# Sheet4.net
KiCad netlist of a schematic drawn in Altium Designer
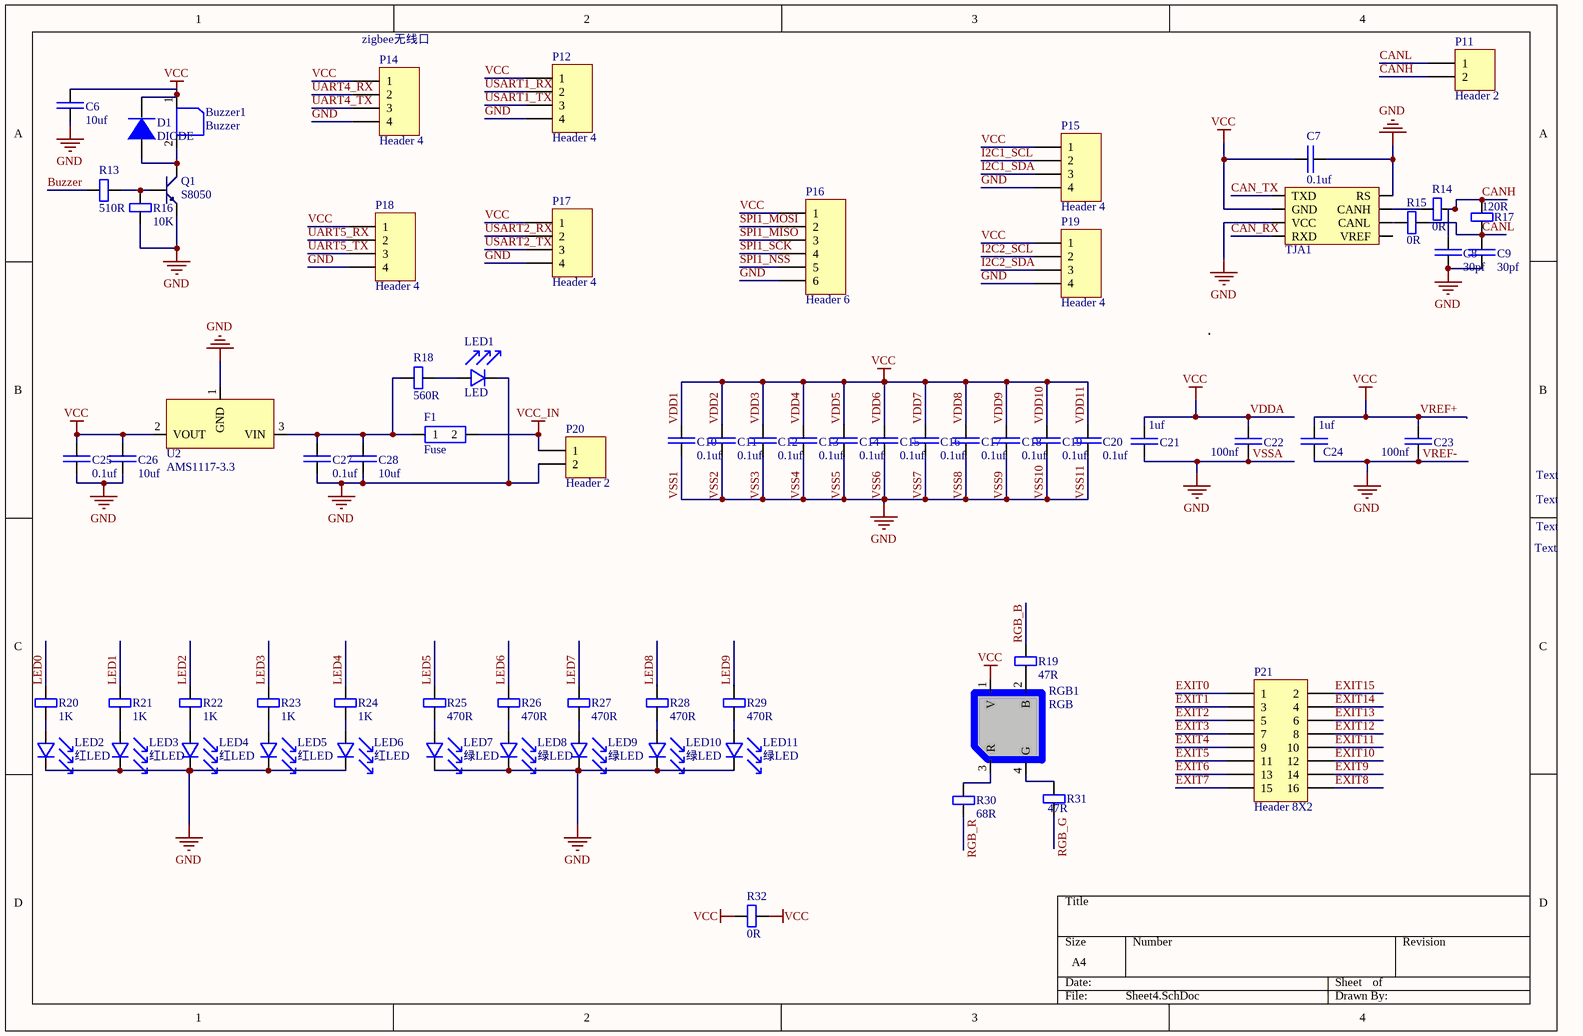
[diagram p0: Sheet4.SchDoc]

(export (version "E")
  (design (tool "Eeschema 10.0.6"))
  (components
    (comp (ref "Buzzer1") (value "Buzzer") (footprint "BUZZER") (libsource (lib "Schlib1") (part "Buzzer")))
    (comp (ref "C6") (value "10uf") (footprint "0402") (libsource (lib "Schlib1") (part "C")))
    (comp (ref "C7") (value "0.1uf") (footprint "0402") (libsource (lib "Schlib1") (part "C")))
    (comp (ref "C8") (value "30pf") (footprint "0402") (libsource (lib "Schlib1") (part "C")))
    (comp (ref "C9") (value "30pf") (footprint "0402") (libsource (lib "Schlib1") (part "C")))
    (comp (ref "C10") (value "0.1uf") (footprint "0402") (libsource (lib "Schlib1") (part "C")))
    (comp (ref "C11") (value "0.1uf") (footprint "0402") (libsource (lib "Schlib1") (part "C")))
    (comp (ref "C12") (value "0.1uf") (footprint "0402") (libsource (lib "Schlib1") (part "C")))
    (comp (ref "C13") (value "0.1uf") (footprint "0402") (libsource (lib "Schlib1") (part "C")))
    (comp (ref "C14") (value "0.1uf") (footprint "0402") (libsource (lib "Schlib1") (part "C")))
    (comp (ref "C15") (value "0.1uf") (footprint "0402") (libsource (lib "Schlib1") (part "C")))
    (comp (ref "C16") (value "0.1uf") (footprint "0402") (libsource (lib "Schlib1") (part "C")))
    (comp (ref "C17") (value "0.1uf") (footprint "0402") (libsource (lib "Schlib1") (part "C")))
    (comp (ref "C18") (value "0.1uf") (footprint "0402") (libsource (lib "Schlib1") (part "C")))
    (comp (ref "C19") (value "0.1uf") (footprint "0402") (libsource (lib "Schlib1") (part "C")))
    (comp (ref "C20") (value "0.1uf") (footprint "0402") (libsource (lib "Schlib1") (part "C")))
    (comp (ref "C21") (value "1uf") (footprint "0402") (libsource (lib "Schlib1") (part "C")))
    (comp (ref "C22") (value "100nf") (footprint "0402") (libsource (lib "Schlib1") (part "C")))
    (comp (ref "C23") (value "100nf") (footprint "0402") (libsource (lib "Schlib1") (part "C")))
    (comp (ref "C24") (value "1uf") (footprint "0402") (libsource (lib "Schlib1") (part "C")))
    (comp (ref "C25") (value "0.1uf") (footprint "0402") (libsource (lib "Schlib1") (part "C")))
    (comp (ref "C26") (value "10uf") (footprint "0402") (libsource (lib "Schlib1") (part "C")))
    (comp (ref "C27") (value "0.1uf") (footprint "0402") (libsource (lib "Schlib1") (part "C")))
    (comp (ref "C28") (value "10uf") (footprint "0402") (libsource (lib "Schlib1") (part "C")))
    (comp (ref "D1") (value "DIODE") (footprint "DIODE") (libsource (lib "Schlib1") (part "DIODE")))
    (comp (ref "F1") (value "Fuse") (footprint "0805") (libsource (lib "Schlib1") (part "Fuse")))
    (comp (ref "LED1") (value "LED") (footprint "0603") (libsource (lib "Schlib1") (part "LED")))
    (comp (ref "LED2") (value "红LED") (footprint "0603") (libsource (lib "Schlib1") (part "LED")))
    (comp (ref "LED3") (value "红LED") (footprint "0603") (libsource (lib "Schlib1") (part "LED")))
    (comp (ref "LED4") (value "红LED") (footprint "0603") (libsource (lib "Schlib1") (part "LED")))
    (comp (ref "LED5") (value "红LED") (footprint "0603") (libsource (lib "Schlib1") (part "LED")))
    (comp (ref "LED6") (value "红LED") (footprint "0603") (libsource (lib "Schlib1") (part "LED")))
    (comp (ref "LED7") (value "绿LED") (footprint "0603") (libsource (lib "Schlib1") (part "LED")))
    (comp (ref "LED8") (value "绿LED") (footprint "0603") (libsource (lib "Schlib1") (part "LED")))
    (comp (ref "LED9") (value "绿LED") (footprint "0603") (libsource (lib "Schlib1") (part "LED")))
    (comp (ref "LED10") (value "绿LED") (footprint "0603") (libsource (lib "Schlib1") (part "LED")))
    (comp (ref "LED11") (value "绿LED") (footprint "0603") (libsource (lib "Schlib1") (part "LED")))
    (comp (ref "P11")
      (value "Header 2")
      (footprint "GH1.25_2P")
      (description "Header, 2-Pin")
      (fields (field (name "PUBLISHER") "Altium Limited"))
      (libsource (lib "Miscellaneous Connectors") (part "Header 2"))
    )
    (comp (ref "P12")
      (value "Header 4")
      (footprint "GH1.25_4P")
      (description "Header, 4-Pin")
      (fields (field (name "PUBLISHER") "Altium Limited"))
      (libsource (lib "Miscellaneous Connectors") (part "Header 4"))
    )
    (comp (ref "P14")
      (value "Header 4")
      (footprint "GH1.25_4P")
      (description "Header, 4-Pin")
      (fields (field (name "PUBLISHER") "Altium Limited"))
      (libsource (lib "Miscellaneous Connectors") (part "Header 4"))
    )
    (comp (ref "P15")
      (value "Header 4")
      (footprint "GH1.25_4P")
      (description "Header, 4-Pin")
      (fields (field (name "PUBLISHER") "Altium Limited"))
      (libsource (lib "Miscellaneous Connectors") (part "Header 4"))
    )
    (comp (ref "P16")
      (value "Header 6")
      (footprint "HDR1X6")
      (description "Header, 6-Pin")
      (fields (field (name "PUBLISHER") "Altium Limited"))
      (libsource (lib "Miscellaneous Connectors") (part "Header 6"))
    )
    (comp (ref "P17")
      (value "Header 4")
      (footprint "GH1.25_4P")
      (description "Header, 4-Pin")
      (fields (field (name "PUBLISHER") "Altium Limited"))
      (libsource (lib "Miscellaneous Connectors") (part "Header 4"))
    )
    (comp (ref "P18")
      (value "Header 4")
      (footprint "GH1.25_4P")
      (description "Header, 4-Pin")
      (fields (field (name "PUBLISHER") "Altium Limited"))
      (libsource (lib "Miscellaneous Connectors") (part "Header 4"))
    )
    (comp (ref "P19")
      (value "Header 4")
      (footprint "GH1.25_4P")
      (description "Header, 4-Pin")
      (fields (field (name "PUBLISHER") "Altium Limited"))
      (libsource (lib "Miscellaneous Connectors") (part "Header 4"))
    )
    (comp (ref "P20")
      (value "Header 2")
      (footprint "XT30-PW-M")
      (description "Header, 2-Pin")
      (fields (field (name "PUBLISHER") "Altium Limited"))
      (libsource (lib "Miscellaneous Connectors") (part "Header 2"))
    )
    (comp (ref "P21")
      (value "Header 8X2")
      (footprint "HDR2X8")
      (description "Header, 8-Pin, Dual row")
      (fields (field (name "PUBLISHER") "Altium Limited"))
      (libsource (lib "Miscellaneous Connectors") (part "Header 8X2"))
    )
    (comp (ref "Q1")
      (value "S8050")
      (footprint "SOT-23R")
      (description "8050/BCW846/BCW847")
      (libsource (lib "REMOTOR V1.6") (part "NPN"))
    )
    (comp (ref "R13") (value "510R") (footprint "0402") (libsource (lib "Schlib1") (part "R")))
    (comp (ref "R14") (value "0R") (footprint "0402") (libsource (lib "Schlib1") (part "R")))
    (comp (ref "R15") (value "0R") (footprint "0402") (libsource (lib "Schlib1") (part "R")))
    (comp (ref "R16") (value "10K") (footprint "0402") (libsource (lib "Schlib1") (part "R")))
    (comp (ref "R17") (value "120R") (footprint "0402") (libsource (lib "Schlib1") (part "R")))
    (comp (ref "R18") (value "560R") (footprint "0402") (libsource (lib "Schlib1") (part "R")))
    (comp (ref "R19") (value "47R") (footprint "0402") (libsource (lib "Schlib1") (part "R")))
    (comp (ref "R20") (value "1K") (footprint "0402") (libsource (lib "Schlib1") (part "R")))
    (comp (ref "R21") (value "1K") (footprint "0402") (libsource (lib "Schlib1") (part "R")))
    (comp (ref "R22") (value "1K") (footprint "0402") (libsource (lib "Schlib1") (part "R")))
    (comp (ref "R23") (value "1K") (footprint "0402") (libsource (lib "Schlib1") (part "R")))
    (comp (ref "R24") (value "1K") (footprint "0402") (libsource (lib "Schlib1") (part "R")))
    (comp (ref "R25") (value "470R") (footprint "0402") (libsource (lib "Schlib1") (part "R")))
    (comp (ref "R26") (value "470R") (footprint "0402") (libsource (lib "Schlib1") (part "R")))
    (comp (ref "R27") (value "470R") (footprint "0402") (libsource (lib "Schlib1") (part "R")))
    (comp (ref "R28") (value "470R") (footprint "0402") (libsource (lib "Schlib1") (part "R")))
    (comp (ref "R29") (value "470R") (footprint "0402") (libsource (lib "Schlib1") (part "R")))
    (comp (ref "R30") (value "68R") (footprint "0402") (libsource (lib "Schlib1") (part "R")))
    (comp (ref "R31") (value "47R") (footprint "0402") (libsource (lib "Schlib1") (part "R")))
    (comp (ref "R32") (value "0R") (footprint "0603") (libsource (lib "Schlib1") (part "R")))
    (comp (ref "RGB1") (value "RGB") (footprint "RGB_LED") (libsource (lib "Schlib1") (part "RGB")))
    (comp (ref "TJA1") (value "TJA1050") (footprint "TJA1050") (libsource (lib "Schlib1") (part "TJA1050")))
    (comp (ref "U2")
      (value "AMS1117-3.3")
      (footprint "ASM1117")
      (libsource (lib "Schlib1") (part "AMS1117-3.3"))
    )
  )
  (nets
    (net (code "1") (name "/Buzzer") (class "Default")
      (node (ref "R13") (pin "1") (pinfunction "1_1") (pintype "passive"))
    )
    (net (code "2") (name "/CANH") (class "Default")
      (node (ref "C8") (pin "2") (pinfunction "2_2") (pintype "passive"))
      (node (ref "P11") (pin "2") (pinfunction "2_2") (pintype "passive"))
      (node (ref "R14") (pin "2") (pinfunction "2_2") (pintype "passive"))
      (node (ref "R17") (pin "2") (pinfunction "2_2") (pintype "passive"))
    )
    (net (code "3") (name "/CANL") (class "Default")
      (node (ref "C9") (pin "2") (pinfunction "2_2") (pintype "passive"))
      (node (ref "P11") (pin "1") (pinfunction "1_1") (pintype "passive"))
      (node (ref "R15") (pin "2") (pinfunction "2_2") (pintype "passive"))
      (node (ref "R17") (pin "1") (pinfunction "1_1") (pintype "passive"))
    )
    (net (code "4") (name "/CAN_RX") (class "Default")
      (node (ref "TJA1") (pin "4") (pinfunction "RXD_4") (pintype "passive"))
    )
    (net (code "5") (name "/CAN_TX") (class "Default")
      (node (ref "TJA1") (pin "1") (pinfunction "TXD_1") (pintype "passive"))
    )
    (net (code "6") (name "/EXIT0") (class "Default")
      (node (ref "P21") (pin "1") (pinfunction "1_1") (pintype "passive"))
    )
    (net (code "7") (name "/EXIT1") (class "Default")
      (node (ref "P21") (pin "3") (pinfunction "3_3") (pintype "passive"))
    )
    (net (code "8") (name "/EXIT2") (class "Default")
      (node (ref "P21") (pin "5") (pinfunction "5_5") (pintype "passive"))
    )
    (net (code "9") (name "/EXIT3") (class "Default")
      (node (ref "P21") (pin "7") (pinfunction "7_7") (pintype "passive"))
    )
    (net (code "10") (name "/EXIT4") (class "Default")
      (node (ref "P21") (pin "9") (pinfunction "9_9") (pintype "passive"))
    )
    (net (code "11") (name "/EXIT5") (class "Default")
      (node (ref "P21") (pin "11") (pinfunction "11_11") (pintype "passive"))
    )
    (net (code "12") (name "/EXIT6") (class "Default")
      (node (ref "P21") (pin "13") (pinfunction "13_13") (pintype "passive"))
    )
    (net (code "13") (name "/EXIT7") (class "Default")
      (node (ref "P21") (pin "15") (pinfunction "15_15") (pintype "passive"))
    )
    (net (code "14") (name "/EXIT8") (class "Default")
      (node (ref "P21") (pin "16") (pinfunction "16_16") (pintype "passive"))
    )
    (net (code "15") (name "/EXIT9") (class "Default")
      (node (ref "P21") (pin "14") (pinfunction "14_14") (pintype "passive"))
    )
    (net (code "16") (name "/EXIT10") (class "Default")
      (node (ref "P21") (pin "12") (pinfunction "12_12") (pintype "passive"))
    )
    (net (code "17") (name "/EXIT11") (class "Default")
      (node (ref "P21") (pin "10") (pinfunction "10_10") (pintype "passive"))
    )
    (net (code "18") (name "/EXIT12") (class "Default")
      (node (ref "P21") (pin "8") (pinfunction "8_8") (pintype "passive"))
    )
    (net (code "19") (name "/EXIT13") (class "Default")
      (node (ref "P21") (pin "6") (pinfunction "6_6") (pintype "passive"))
    )
    (net (code "20") (name "/EXIT14") (class "Default")
      (node (ref "P21") (pin "4") (pinfunction "4_4") (pintype "passive"))
    )
    (net (code "21") (name "/EXIT15") (class "Default")
      (node (ref "P21") (pin "2") (pinfunction "2_2") (pintype "passive"))
    )
    (net (code "22") (name "/I2C1_SCL") (class "Default")
      (node (ref "P15") (pin "2") (pinfunction "2_2") (pintype "passive"))
    )
    (net (code "23") (name "/I2C1_SDA") (class "Default")
      (node (ref "P15") (pin "3") (pinfunction "3_3") (pintype "passive"))
    )
    (net (code "24") (name "/I2C2_SCL") (class "Default")
      (node (ref "P19") (pin "2") (pinfunction "2_2") (pintype "passive"))
    )
    (net (code "25") (name "/I2C2_SDA") (class "Default")
      (node (ref "P19") (pin "3") (pinfunction "3_3") (pintype "passive"))
    )
    (net (code "26") (name "/LED0") (class "Default")
      (node (ref "R20") (pin "2") (pinfunction "2_2") (pintype "passive"))
    )
    (net (code "27") (name "/LED1") (class "Default")
      (node (ref "R21") (pin "2") (pinfunction "2_2") (pintype "passive"))
    )
    (net (code "28") (name "/LED2") (class "Default")
      (node (ref "R22") (pin "2") (pinfunction "2_2") (pintype "passive"))
    )
    (net (code "29") (name "/LED3") (class "Default")
      (node (ref "R23") (pin "2") (pinfunction "2_2") (pintype "passive"))
    )
    (net (code "30") (name "/LED4") (class "Default")
      (node (ref "R24") (pin "2") (pinfunction "2_2") (pintype "passive"))
    )
    (net (code "31") (name "/LED5") (class "Default")
      (node (ref "R25") (pin "2") (pinfunction "2_2") (pintype "passive"))
    )
    (net (code "32") (name "/LED6") (class "Default")
      (node (ref "R26") (pin "2") (pinfunction "2_2") (pintype "passive"))
    )
    (net (code "33") (name "/LED7") (class "Default")
      (node (ref "R27") (pin "2") (pinfunction "2_2") (pintype "passive"))
    )
    (net (code "34") (name "/LED8") (class "Default")
      (node (ref "R28") (pin "2") (pinfunction "2_2") (pintype "passive"))
    )
    (net (code "35") (name "/LED9") (class "Default")
      (node (ref "R29") (pin "2") (pinfunction "2_2") (pintype "passive"))
    )
    (net (code "36") (name "/RGB_B") (class "Default")
      (node (ref "R19") (pin "2") (pinfunction "2_2") (pintype "passive"))
    )
    (net (code "37") (name "/RGB_G") (class "Default")
      (node (ref "R31") (pin "1") (pinfunction "1_1") (pintype "passive"))
    )
    (net (code "38") (name "/RGB_R") (class "Default")
      (node (ref "R30") (pin "1") (pinfunction "1_1") (pintype "passive"))
    )
    (net (code "39") (name "/SPI1_MISO") (class "Default")
      (node (ref "P16") (pin "3") (pinfunction "3_3") (pintype "passive"))
    )
    (net (code "40") (name "/SPI1_MOSI") (class "Default")
      (node (ref "P16") (pin "2") (pinfunction "2_2") (pintype "passive"))
    )
    (net (code "41") (name "/SPI1_NSS") (class "Default")
      (node (ref "P16") (pin "5") (pinfunction "5_5") (pintype "passive"))
    )
    (net (code "42") (name "/SPI1_SCK") (class "Default")
      (node (ref "P16") (pin "4") (pinfunction "4_4") (pintype "passive"))
    )
    (net (code "43") (name "/UART4_RX") (class "Default")
      (node (ref "P14") (pin "2") (pinfunction "2_2") (pintype "passive"))
    )
    (net (code "44") (name "/UART4_TX") (class "Default")
      (node (ref "P14") (pin "3") (pinfunction "3_3") (pintype "passive"))
    )
    (net (code "45") (name "/UART5_RX") (class "Default")
      (node (ref "P18") (pin "2") (pinfunction "2_2") (pintype "passive"))
    )
    (net (code "46") (name "/UART5_TX") (class "Default")
      (node (ref "P18") (pin "3") (pinfunction "3_3") (pintype "passive"))
    )
    (net (code "47") (name "/USART1_RX") (class "Default")
      (node (ref "P12") (pin "2") (pinfunction "2_2") (pintype "passive"))
    )
    (net (code "48") (name "/USART1_TX") (class "Default")
      (node (ref "P12") (pin "3") (pinfunction "3_3") (pintype "passive"))
    )
    (net (code "49") (name "/USART2_RX") (class "Default")
      (node (ref "P17") (pin "2") (pinfunction "2_2") (pintype "passive"))
    )
    (net (code "50") (name "/USART2_TX") (class "Default")
      (node (ref "P17") (pin "3") (pinfunction "3_3") (pintype "passive"))
    )
    (net (code "51") (name "GND") (class "Default")
      (node (ref "C10") (pin "1") (pinfunction "1_1") (pintype "passive"))
      (node (ref "C11") (pin "1") (pinfunction "1_1") (pintype "passive"))
      (node (ref "C12") (pin "1") (pinfunction "1_1") (pintype "passive"))
      (node (ref "C13") (pin "1") (pinfunction "1_1") (pintype "passive"))
      (node (ref "C14") (pin "1") (pinfunction "1_1") (pintype "passive"))
      (node (ref "C15") (pin "1") (pinfunction "1_1") (pintype "passive"))
      (node (ref "C16") (pin "1") (pinfunction "1_1") (pintype "passive"))
      (node (ref "C17") (pin "1") (pinfunction "1_1") (pintype "passive"))
      (node (ref "C18") (pin "1") (pinfunction "1_1") (pintype "passive"))
      (node (ref "C19") (pin "1") (pinfunction "1_1") (pintype "passive"))
      (node (ref "C20") (pin "1") (pinfunction "1_1") (pintype "passive"))
      (node (ref "C21") (pin "1") (pinfunction "1_1") (pintype "passive"))
      (node (ref "C22") (pin "1") (pinfunction "1_1") (pintype "passive"))
      (node (ref "C23") (pin "1") (pinfunction "1_1") (pintype "passive"))
      (node (ref "C24") (pin "1") (pinfunction "1_1") (pintype "passive"))
      (node (ref "C25") (pin "2") (pinfunction "2_2") (pintype "passive"))
      (node (ref "C26") (pin "2") (pinfunction "2_2") (pintype "passive"))
      (node (ref "C27") (pin "2") (pinfunction "2_2") (pintype "passive"))
      (node (ref "C28") (pin "2") (pinfunction "2_2") (pintype "passive"))
      (node (ref "C6") (pin "1") (pinfunction "1_1") (pintype "passive"))
      (node (ref "C7") (pin "2") (pinfunction "2_2") (pintype "passive"))
      (node (ref "C8") (pin "1") (pinfunction "1_1") (pintype "passive"))
      (node (ref "C9") (pin "1") (pinfunction "1_1") (pintype "passive"))
      (node (ref "LED1") (pin "2") (pinfunction "2_2") (pintype "passive"))
      (node (ref "LED10") (pin "2") (pinfunction "2_2") (pintype "passive"))
      (node (ref "LED11") (pin "2") (pinfunction "2_2") (pintype "passive"))
      (node (ref "LED2") (pin "2") (pinfunction "2_2") (pintype "passive"))
      (node (ref "LED3") (pin "2") (pinfunction "2_2") (pintype "passive"))
      (node (ref "LED4") (pin "2") (pinfunction "2_2") (pintype "passive"))
      (node (ref "LED5") (pin "2") (pinfunction "2_2") (pintype "passive"))
      (node (ref "LED6") (pin "2") (pinfunction "2_2") (pintype "passive"))
      (node (ref "LED7") (pin "2") (pinfunction "2_2") (pintype "passive"))
      (node (ref "LED8") (pin "2") (pinfunction "2_2") (pintype "passive"))
      (node (ref "LED9") (pin "2") (pinfunction "2_2") (pintype "passive"))
      (node (ref "P12") (pin "4") (pinfunction "4_4") (pintype "passive"))
      (node (ref "P14") (pin "4") (pinfunction "4_4") (pintype "passive"))
      (node (ref "P15") (pin "4") (pinfunction "4_4") (pintype "passive"))
      (node (ref "P16") (pin "6") (pinfunction "6_6") (pintype "passive"))
      (node (ref "P17") (pin "4") (pinfunction "4_4") (pintype "passive"))
      (node (ref "P18") (pin "4") (pinfunction "4_4") (pintype "passive"))
      (node (ref "P19") (pin "4") (pinfunction "4_4") (pintype "passive"))
      (node (ref "P20") (pin "2") (pinfunction "2_2") (pintype "passive"))
      (node (ref "Q1") (pin "1") (pinfunction "E_1") (pintype "passive"))
      (node (ref "R16") (pin "1") (pinfunction "1_1") (pintype "passive"))
      (node (ref "TJA1") (pin "3") (pinfunction "VCC_3") (pintype "passive"))
      (node (ref "TJA1") (pin "8") (pinfunction "RS_8") (pintype "passive"))
      (node (ref "U2") (pin "1") (pinfunction "GND_1") (pintype "passive"))
    )
    (net (code "52") (name "Net-(LED1-Pad1)") (class "Default")
      (node (ref "LED1") (pin "1") (pinfunction "1_1") (pintype "passive"))
      (node (ref "R18") (pin "2") (pinfunction "2_2") (pintype "passive"))
    )
    (net (code "53") (name "Net-(LED2-Pad1)") (class "Default")
      (node (ref "LED2") (pin "1") (pinfunction "1_1") (pintype "passive"))
      (node (ref "R20") (pin "1") (pinfunction "1_1") (pintype "passive"))
    )
    (net (code "54") (name "Net-(LED3-Pad1)") (class "Default")
      (node (ref "LED3") (pin "1") (pinfunction "1_1") (pintype "passive"))
      (node (ref "R21") (pin "1") (pinfunction "1_1") (pintype "passive"))
    )
    (net (code "55") (name "Net-(LED4-Pad1)") (class "Default")
      (node (ref "LED4") (pin "1") (pinfunction "1_1") (pintype "passive"))
      (node (ref "R22") (pin "1") (pinfunction "1_1") (pintype "passive"))
    )
    (net (code "56") (name "Net-(LED5-Pad1)") (class "Default")
      (node (ref "LED5") (pin "1") (pinfunction "1_1") (pintype "passive"))
      (node (ref "R23") (pin "1") (pinfunction "1_1") (pintype "passive"))
    )
    (net (code "57") (name "Net-(LED6-Pad1)") (class "Default")
      (node (ref "LED6") (pin "1") (pinfunction "1_1") (pintype "passive"))
      (node (ref "R24") (pin "1") (pinfunction "1_1") (pintype "passive"))
    )
    (net (code "58") (name "Net-(LED7-Pad1)") (class "Default")
      (node (ref "LED7") (pin "1") (pinfunction "1_1") (pintype "passive"))
      (node (ref "R25") (pin "1") (pinfunction "1_1") (pintype "passive"))
    )
    (net (code "59") (name "Net-(LED8-Pad1)") (class "Default")
      (node (ref "LED8") (pin "1") (pinfunction "1_1") (pintype "passive"))
      (node (ref "R26") (pin "1") (pinfunction "1_1") (pintype "passive"))
    )
    (net (code "60") (name "Net-(LED9-Pad1)") (class "Default")
      (node (ref "LED9") (pin "1") (pinfunction "1_1") (pintype "passive"))
      (node (ref "R27") (pin "1") (pinfunction "1_1") (pintype "passive"))
    )
    (net (code "61") (name "Net-(LED10-Pad1)") (class "Default")
      (node (ref "LED10") (pin "1") (pinfunction "1_1") (pintype "passive"))
      (node (ref "R28") (pin "1") (pinfunction "1_1") (pintype "passive"))
    )
    (net (code "62") (name "Net-(LED11-Pad1)") (class "Default")
      (node (ref "LED11") (pin "1") (pinfunction "1_1") (pintype "passive"))
      (node (ref "R29") (pin "1") (pinfunction "1_1") (pintype "passive"))
    )
    (net (code "63") (name "Net-(Q1-B)") (class "Default")
      (node (ref "Q1") (pin "2") (pinfunction "B_2") (pintype "passive"))
      (node (ref "R13") (pin "2") (pinfunction "2_2") (pintype "passive"))
      (node (ref "R16") (pin "2") (pinfunction "2_2") (pintype "passive"))
    )
    (net (code "64") (name "Net-(Q1-C)") (class "Default")
      (node (ref "Buzzer1") (pin "2") (pinfunction "2_2") (pintype "passive"))
      (node (ref "D1") (pin "2") (pinfunction "2_2") (pintype "passive"))
      (node (ref "Q1") (pin "3") (pinfunction "C_3") (pintype "passive"))
    )
    (net (code "65") (name "Net-(RGB1-B)") (class "Default")
      (node (ref "R19") (pin "1") (pinfunction "1_1") (pintype "passive"))
      (node (ref "RGB1") (pin "2") (pinfunction "B_2") (pintype "passive"))
    )
    (net (code "66") (name "Net-(RGB1-G)") (class "Default")
      (node (ref "R31") (pin "2") (pinfunction "2_2") (pintype "passive"))
      (node (ref "RGB1") (pin "4") (pinfunction "G_4") (pintype "passive"))
    )
    (net (code "67") (name "Net-(RGB1-R)") (class "Default")
      (node (ref "R30") (pin "2") (pinfunction "2_2") (pintype "passive"))
      (node (ref "RGB1") (pin "3") (pinfunction "R_3") (pintype "passive"))
    )
    (net (code "68") (name "Net-(TJA1-CANH)") (class "Default")
      (node (ref "R14") (pin "1") (pinfunction "1_1") (pintype "passive"))
      (node (ref "TJA1") (pin "7") (pinfunction "CANH_7") (pintype "passive"))
    )
    (net (code "69") (name "Net-(TJA1-CANL)") (class "Default")
      (node (ref "R15") (pin "1") (pinfunction "1_1") (pintype "passive"))
      (node (ref "TJA1") (pin "6") (pinfunction "CANL_6") (pintype "passive"))
    )
    (net (code "70") (name "Net-(U2-VIN)") (class "Default")
      (node (ref "C27") (pin "1") (pinfunction "1_1") (pintype "passive"))
      (node (ref "C28") (pin "1") (pinfunction "1_1") (pintype "passive"))
      (node (ref "F1") (pin "1") (pinfunction "1_1") (pintype "passive"))
      (node (ref "R18") (pin "1") (pinfunction "1_1") (pintype "passive"))
      (node (ref "U2") (pin "3") (pinfunction "VIN_3") (pintype "passive"))
    )
    (net (code "71") (name "VCC") (class "Default")
      (node (ref "Buzzer1") (pin "1") (pinfunction "1_1") (pintype "passive"))
      (node (ref "C10") (pin "2") (pinfunction "2_2") (pintype "passive"))
      (node (ref "C11") (pin "2") (pinfunction "2_2") (pintype "passive"))
      (node (ref "C12") (pin "2") (pinfunction "2_2") (pintype "passive"))
      (node (ref "C13") (pin "2") (pinfunction "2_2") (pintype "passive"))
      (node (ref "C14") (pin "2") (pinfunction "2_2") (pintype "passive"))
      (node (ref "C15") (pin "2") (pinfunction "2_2") (pintype "passive"))
      (node (ref "C16") (pin "2") (pinfunction "2_2") (pintype "passive"))
      (node (ref "C17") (pin "2") (pinfunction "2_2") (pintype "passive"))
      (node (ref "C18") (pin "2") (pinfunction "2_2") (pintype "passive"))
      (node (ref "C19") (pin "2") (pinfunction "2_2") (pintype "passive"))
      (node (ref "C20") (pin "2") (pinfunction "2_2") (pintype "passive"))
      (node (ref "C21") (pin "2") (pinfunction "2_2") (pintype "passive"))
      (node (ref "C22") (pin "2") (pinfunction "2_2") (pintype "passive"))
      (node (ref "C23") (pin "2") (pinfunction "2_2") (pintype "passive"))
      (node (ref "C24") (pin "2") (pinfunction "2_2") (pintype "passive"))
      (node (ref "C25") (pin "1") (pinfunction "1_1") (pintype "passive"))
      (node (ref "C26") (pin "1") (pinfunction "1_1") (pintype "passive"))
      (node (ref "C6") (pin "2") (pinfunction "2_2") (pintype "passive"))
      (node (ref "C7") (pin "1") (pinfunction "1_1") (pintype "passive"))
      (node (ref "D1") (pin "1") (pinfunction "1_1") (pintype "passive"))
      (node (ref "P12") (pin "1") (pinfunction "1_1") (pintype "passive"))
      (node (ref "P14") (pin "1") (pinfunction "1_1") (pintype "passive"))
      (node (ref "P15") (pin "1") (pinfunction "1_1") (pintype "passive"))
      (node (ref "P16") (pin "1") (pinfunction "1_1") (pintype "passive"))
      (node (ref "P17") (pin "1") (pinfunction "1_1") (pintype "passive"))
      (node (ref "P18") (pin "1") (pinfunction "1_1") (pintype "passive"))
      (node (ref "P19") (pin "1") (pinfunction "1_1") (pintype "passive"))
      (node (ref "R32") (pin "1") (pinfunction "1_1") (pintype "passive"))
      (node (ref "R32") (pin "2") (pinfunction "2_2") (pintype "passive"))
      (node (ref "RGB1") (pin "1") (pinfunction "V_1") (pintype "passive"))
      (node (ref "TJA1") (pin "2") (pinfunction "GND_2") (pintype "passive"))
      (node (ref "U2") (pin "2") (pinfunction "VOUT_2") (pintype "passive"))
    )
    (net (code "72") (name "VCC_IN") (class "Default")
      (node (ref "F1") (pin "2") (pinfunction "2_2") (pintype "passive"))
      (node (ref "P20") (pin "1") (pinfunction "1_1") (pintype "passive"))
    )
    (net (code "73") (name "unconnected-(TJA1-VREF-Pad5)") (class "Default")
      (node (ref "TJA1") (pin "5") (pinfunction "VREF_5") (pintype "passive"))
    )
  )
)
